# schematic.net
KiCad netlist of a schematic drawn in Altium Designer
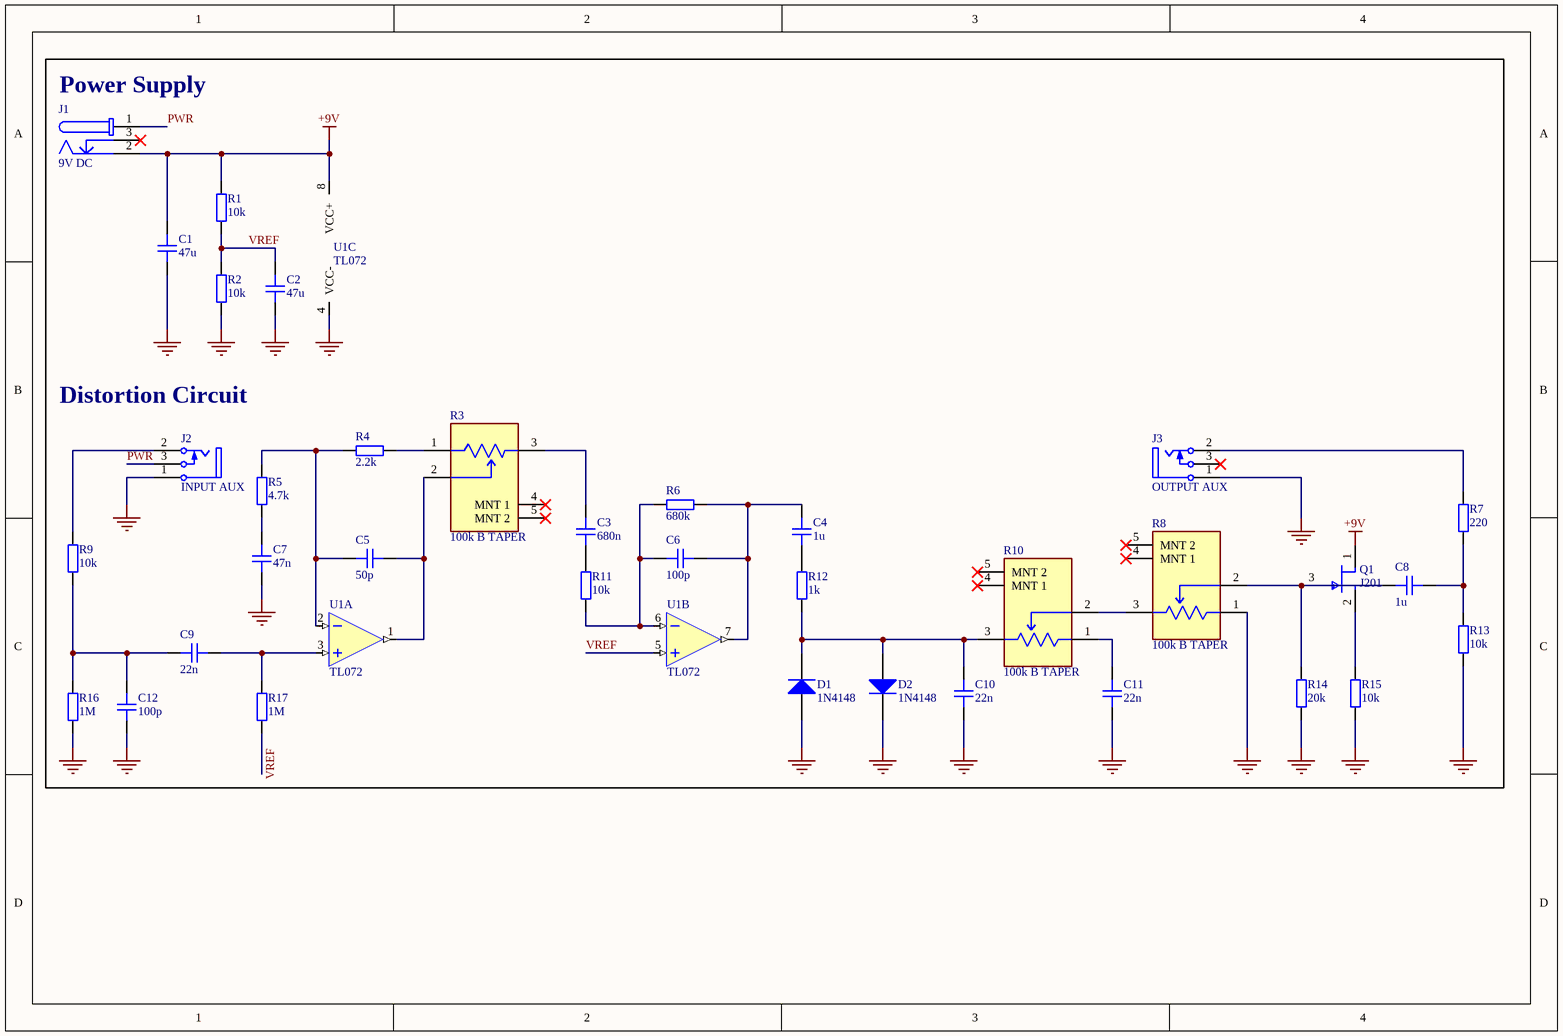
[diagram p0: schematic.SchDoc]

(export (version "E")
  (design (tool "Eeschema 10.0.6"))
  (components
    (comp (ref "C1")
      (value "47u")
      (footprint "CAP_0603")
      (description "Capacitor SMD 0603")
      (libsource (lib "Schematic-Lib-PhilsLab") (part "CAP_0603"))
    )
    (comp (ref "C2")
      (value "47u")
      (footprint "CAP_0603")
      (description "Capacitor SMD 0603")
      (libsource (lib "Schematic-Lib-PhilsLab") (part "CAP_0603"))
    )
    (comp (ref "C3")
      (value "680n")
      (footprint "CAP_0603")
      (description "Capacitor SMD 0603")
      (libsource (lib "Schematic-Lib-PhilsLab") (part "CAP_0603"))
    )
    (comp (ref "C4")
      (value "1u")
      (footprint "CAP_0603")
      (description "Capacitor SMD 0603")
      (libsource (lib "Schematic-Lib-PhilsLab") (part "CAP_0603"))
    )
    (comp (ref "C5")
      (value "50p")
      (footprint "CAP_0603")
      (description "Capacitor SMD 0603")
      (libsource (lib "Schematic-Lib-PhilsLab") (part "CAP_0603"))
    )
    (comp (ref "C6")
      (value "100p")
      (footprint "CAP_0603")
      (description "Capacitor SMD 0603")
      (libsource (lib "Schematic-Lib-PhilsLab") (part "CAP_0603"))
    )
    (comp (ref "C7")
      (value "47n")
      (footprint "CAP_0603")
      (description "Capacitor SMD 0603")
      (libsource (lib "Schematic-Lib-PhilsLab") (part "CAP_0603"))
    )
    (comp (ref "C8")
      (value "1u")
      (footprint "CAP_0603")
      (description "Capacitor SMD 0603")
      (libsource (lib "Schematic-Lib-PhilsLab") (part "CAP_0603"))
    )
    (comp (ref "C9")
      (value "22n")
      (footprint "CAP_0603")
      (description "Capacitor SMD 0603")
      (libsource (lib "Schematic-Lib-PhilsLab") (part "CAP_0603"))
    )
    (comp (ref "C10")
      (value "22n")
      (footprint "CAP_0603")
      (description "Capacitor SMD 0603")
      (libsource (lib "Schematic-Lib-PhilsLab") (part "CAP_0603"))
    )
    (comp (ref "C11")
      (value "22n")
      (footprint "CAP_0603")
      (description "Capacitor SMD 0603")
      (libsource (lib "Schematic-Lib-PhilsLab") (part "CAP_0603"))
    )
    (comp (ref "C12")
      (value "100p")
      (footprint "CAP_0603")
      (description "Capacitor SMD 0603")
      (libsource (lib "Schematic-Lib-PhilsLab") (part "CAP_0603"))
    )
    (comp (ref "D1")
      (value "1N4148")
      (footprint "DIOD-SOD323-2-A_V")
      (description "Fast Switching Diode, 75 V, 0.3 A, -65 to 150 degC, 2-Pin SOD323, RoHS, Tape and Reel")
      (libsource (lib "Altium Content Vault") (part "D-AK-2"))
    )
    (comp (ref "D2")
      (value "1N4148")
      (footprint "DIOD-SOD323-2-A_V")
      (description "Fast Switching Diode, 75 V, 0.3 A, -65 to 150 degC, 2-Pin SOD323, RoHS, Tape and Reel")
      (libsource (lib "Altium Content Vault") (part "D-AK-2"))
    )
    (comp (ref "J1")
      (value "9V DC")
      (footprint "694106301002")
      (libsource (lib "Altium Content Vault") (part "DC Power Jack"))
    )
    (comp (ref "J2")
      (value "INPUT AUX")
      (footprint "SWIT-PJRAN1X1U01X_V")
      (description "Female Phono Jack, 3 Position, Height 13 mm, Tail Length 4 mm, RoHS, Bulk")
      (fields (field (name "TOLERANCE") "10%"))
      (libsource (lib "Altium Content Vault") (part "JACK-2CD3-TN"))
    )
    (comp (ref "J3")
      (value "OUTPUT AUX")
      (footprint "SWIT-PJRAN1X1U01X_V")
      (description "Female Phono Jack, 3 Position, Height 13 mm, Tail Length 4 mm, RoHS, Bulk")
      (fields (field (name "TOLERANCE") "10%"))
      (libsource (lib "Altium Content Vault") (part "JACK-2CD3-TN"))
    )
    (comp (ref "Q1")
      (value "J201")
      (footprint "FP-318BM-IPC_C")
      (description "JFET N-CH 40V 350MW SOT23")
      (fields
        (field (name "MANUFACTURER") "ON Semiconductor")
        (field (name "OCTOPART") "https://octopart.com/mmbfj201-on+semiconductor-84330255")
      )
      (libsource (lib "Altium Content Vault") (part "14398f7355be6f33287877db3ee21c7"))
    )
    (comp (ref "R1")
      (value "10k")
      (footprint "RES_0603")
      (description "Resistor SMD 0603")
      (libsource (lib "Schematic-Lib-PhilsLab") (part "RES_0603"))
    )
    (comp (ref "R2")
      (value "10k")
      (footprint "RES_0603")
      (description "Resistor SMD 0603")
      (libsource (lib "Schematic-Lib-PhilsLab") (part "RES_0603"))
    )
    (comp (ref "R3")
      (value "100k B TAPER")
      (footprint "FP-PTV09A-4-MFG")
      (description "POT 10K OHM 1/20W CARBON LINEAR")
      (fields (field (name "MANUFACTURER PART NUMBER") "PTV09A-4020U-B103") (field (name "TOLERANCE") "20%"))
      (libsource (lib "") (part "3454c451b146ec4d4239c7813666f62_1"))
    )
    (comp (ref "R4")
      (value "2.2k")
      (footprint "RES_0603")
      (description "Resistor SMD 0603")
      (libsource (lib "Schematic-Lib-PhilsLab") (part "RES_0603"))
    )
    (comp (ref "R5")
      (value "4.7k")
      (footprint "RES_0603")
      (description "Resistor SMD 0603")
      (libsource (lib "Schematic-Lib-PhilsLab") (part "RES_0603"))
    )
    (comp (ref "R6")
      (value "680k")
      (footprint "RES_0603")
      (description "Resistor SMD 0603")
      (libsource (lib "Schematic-Lib-PhilsLab") (part "RES_0603"))
    )
    (comp (ref "R7")
      (value "220")
      (footprint "RES_0603")
      (description "Resistor SMD 0603")
      (libsource (lib "Schematic-Lib-PhilsLab") (part "RES_0603"))
    )
    (comp (ref "R8")
      (value "100k B TAPER")
      (footprint "FP-PTV09A-4-MFG")
      (description "POT 10K OHM 1/20W CARBON LINEAR")
      (fields (field (name "MANUFACTURER PART NUMBER") "PTV09A-4020U-B103") (field (name "TOLERANCE") "20%"))
      (libsource (lib "Altium Content Vault") (part "3454c451b146ec4d4239c7813666f62"))
    )
    (comp (ref "R9")
      (value "10k")
      (footprint "RES_0603")
      (description "Resistor SMD 0603")
      (libsource (lib "Schematic-Lib-PhilsLab") (part "RES_0603"))
    )
    (comp (ref "R10")
      (value "100k B TAPER")
      (footprint "FP-PTV09A-4-MFG")
      (description "POT 10K OHM 1/20W CARBON LINEAR")
      (fields (field (name "MANUFACTURER PART NUMBER") "PTV09A-4020U-B103") (field (name "TOLERANCE") "20%"))
      (libsource (lib "Altium Content Vault") (part "3454c451b146ec4d4239c7813666f62"))
    )
    (comp (ref "R11")
      (value "10k")
      (footprint "RES_0603")
      (description "Resistor SMD 0603")
      (libsource (lib "Schematic-Lib-PhilsLab") (part "RES_0603"))
    )
    (comp (ref "R12")
      (value "1k")
      (footprint "RES_0603")
      (description "Resistor SMD 0603")
      (libsource (lib "Schematic-Lib-PhilsLab") (part "RES_0603"))
    )
    (comp (ref "R13")
      (value "10k")
      (footprint "RES_0603")
      (description "Resistor SMD 0603")
      (libsource (lib "Schematic-Lib-PhilsLab") (part "RES_0603"))
    )
    (comp (ref "R14")
      (value "20k")
      (footprint "RES_0603")
      (description "Resistor SMD 0603")
      (libsource (lib "Schematic-Lib-PhilsLab") (part "RES_0603"))
    )
    (comp (ref "R15")
      (value "10k")
      (footprint "RES_0603")
      (description "Resistor SMD 0603")
      (libsource (lib "Schematic-Lib-PhilsLab") (part "RES_0603"))
    )
    (comp (ref "R16")
      (value "1M")
      (footprint "RES_0603")
      (description "Resistor SMD 0603")
      (libsource (lib "Schematic-Lib-PhilsLab") (part "RES_0603"))
    )
    (comp (ref "R17")
      (value "1M")
      (footprint "RES_0603")
      (description "Resistor SMD 0603")
      (libsource (lib "Schematic-Lib-PhilsLab") (part "RES_0603"))
    )
    (comp (ref "U1")
      (value "TL072")
      (footprint "SOIC-8")
      (description "Dual JFET Low-Noise Operational Amplifiers")
      (fields
        (field (name "MANUFACTURER") "STMicroelectronics")
        (field (name "MANUFACTURER PART NUMBER") "TL072CDT")
      )
      (libsource (lib "Schematic-Lib-PhilsLab") (part "TL072CDT"))
    )
  )
  (nets
    (net (code "1") (name "+9V") (class "Default")
      (node (ref "C1") (pin "1") (pinfunction "1_1") (pintype "passive"))
      (node (ref "J1") (pin "2") (pinfunction "2_2") (pintype "passive"))
      (node (ref "Q1") (pin "1") (pinfunction "D_1") (pintype "passive"))
      (node (ref "R1") (pin "2") (pinfunction "2_2") (pintype "passive"))
      (node (ref "U1") (pin "8") (pinfunction "VCC+_8") (pintype "passive"))
    )
    (net (code "2") (name "/PWR") (class "Default")
      (node (ref "J1") (pin "1") (pinfunction "1_1") (pintype "passive"))
      (node (ref "J2") (pin "3") (pinfunction "SHUNT_3") (pintype "passive"))
    )
    (net (code "3") (name "/VREF") (class "Default")
      (node (ref "C2") (pin "1") (pinfunction "1_1") (pintype "passive"))
      (node (ref "R1") (pin "1") (pinfunction "1_1") (pintype "passive"))
      (node (ref "R17") (pin "1") (pinfunction "1_1") (pintype "passive"))
      (node (ref "R2") (pin "2") (pinfunction "2_2") (pintype "passive"))
      (node (ref "U1") (pin "5") (pinfunction "2IN+_5") (pintype "input"))
    )
    (net (code "4") (name "GND") (class "Default")
      (node (ref "C1") (pin "2") (pinfunction "2_2") (pintype "passive"))
      (node (ref "C10") (pin "1") (pinfunction "1_1") (pintype "passive"))
      (node (ref "C11") (pin "1") (pinfunction "1_1") (pintype "passive"))
      (node (ref "C12") (pin "1") (pinfunction "1_1") (pintype "passive"))
      (node (ref "C2") (pin "2") (pinfunction "2_2") (pintype "passive"))
      (node (ref "C7") (pin "2") (pinfunction "2_2") (pintype "passive"))
      (node (ref "D1") (pin "1") (pinfunction "A_1") (pintype "passive"))
      (node (ref "D2") (pin "2") (pinfunction "K_2") (pintype "passive"))
      (node (ref "J2") (pin "1") (pinfunction "SLEEVE_1") (pintype "passive"))
      (node (ref "J3") (pin "1") (pinfunction "SLEEVE_1") (pintype "passive"))
      (node (ref "R13") (pin "1") (pinfunction "1_1") (pintype "passive"))
      (node (ref "R14") (pin "1") (pinfunction "1_1") (pintype "passive"))
      (node (ref "R15") (pin "1") (pinfunction "1_1") (pintype "passive"))
      (node (ref "R16") (pin "1") (pinfunction "1_1") (pintype "passive"))
      (node (ref "R2") (pin "1") (pinfunction "1_1") (pintype "passive"))
      (node (ref "R8") (pin "1") (pinfunction "1_1") (pintype "passive"))
      (node (ref "U1") (pin "4") (pinfunction "VCC-_4") (pintype "passive"))
    )
    (net (code "5") (name "Net-(C3-Pad1)") (class "Default")
      (node (ref "C3") (pin "1") (pinfunction "1_1") (pintype "passive"))
      (node (ref "R3") (pin "3") (pinfunction "3_3") (pintype "passive"))
    )
    (net (code "6") (name "Net-(C3-Pad2)") (class "Default")
      (node (ref "C3") (pin "2") (pinfunction "2_2") (pintype "passive"))
      (node (ref "R11") (pin "2") (pinfunction "2_2") (pintype "passive"))
    )
    (net (code "7") (name "Net-(C4-Pad1)") (class "Default")
      (node (ref "C4") (pin "1") (pinfunction "1_1") (pintype "passive"))
      (node (ref "R12") (pin "2") (pinfunction "2_2") (pintype "passive"))
    )
    (net (code "8") (name "Net-(C7-Pad1)") (class "Default")
      (node (ref "C7") (pin "1") (pinfunction "1_1") (pintype "passive"))
      (node (ref "R5") (pin "1") (pinfunction "1_1") (pintype "passive"))
    )
    (net (code "9") (name "Net-(C8-Pad1)") (class "Default")
      (node (ref "C8") (pin "1") (pinfunction "1_1") (pintype "passive"))
      (node (ref "R13") (pin "2") (pinfunction "2_2") (pintype "passive"))
      (node (ref "R7") (pin "1") (pinfunction "1_1") (pintype "passive"))
    )
    (net (code "10") (name "Net-(C11-Pad2)") (class "Default")
      (node (ref "C11") (pin "2") (pinfunction "2_2") (pintype "passive"))
      (node (ref "R10") (pin "1") (pinfunction "1_1") (pintype "passive"))
    )
    (net (code "11") (name "Net-(C12-Pad2)") (class "Default")
      (node (ref "C12") (pin "2") (pinfunction "2_2") (pintype "passive"))
      (node (ref "C9") (pin "2") (pinfunction "2_2") (pintype "passive"))
      (node (ref "R16") (pin "2") (pinfunction "2_2") (pintype "passive"))
      (node (ref "R9") (pin "1") (pinfunction "1_1") (pintype "passive"))
    )
    (net (code "12") (name "Net-(D1-K)") (class "Default")
      (node (ref "C10") (pin "2") (pinfunction "2_2") (pintype "passive"))
      (node (ref "D1") (pin "2") (pinfunction "K_2") (pintype "passive"))
      (node (ref "D2") (pin "1") (pinfunction "A_1") (pintype "passive"))
      (node (ref "R10") (pin "3") (pinfunction "3_3") (pintype "passive"))
      (node (ref "R12") (pin "1") (pinfunction "1_1") (pintype "passive"))
    )
    (net (code "13") (name "Net-(J2-TIP)") (class "Default")
      (node (ref "J2") (pin "2") (pinfunction "TIP_2") (pintype "passive"))
      (node (ref "R9") (pin "2") (pinfunction "2_2") (pintype "passive"))
    )
    (net (code "14") (name "Net-(J3-TIP)") (class "Default")
      (node (ref "J3") (pin "2") (pinfunction "TIP_2") (pintype "passive"))
      (node (ref "R7") (pin "2") (pinfunction "2_2") (pintype "passive"))
    )
    (net (code "15") (name "Net-(Q1-G)") (class "Default")
      (node (ref "C8") (pin "2") (pinfunction "2_2") (pintype "passive"))
      (node (ref "Q1") (pin "3") (pinfunction "G_3") (pintype "passive"))
      (node (ref "R14") (pin "2") (pinfunction "2_2") (pintype "passive"))
      (node (ref "R8") (pin "2") (pinfunction "2_2") (pintype "passive"))
    )
    (net (code "16") (name "Net-(Q1-S)") (class "Default")
      (node (ref "Q1") (pin "2") (pinfunction "S_2") (pintype "passive"))
      (node (ref "R15") (pin "2") (pinfunction "2_2") (pintype "passive"))
    )
    (net (code "17") (name "Net-(R3-Pad1)") (class "Default")
      (node (ref "R3") (pin "1") (pinfunction "1_1") (pintype "passive"))
      (node (ref "R4") (pin "1") (pinfunction "1_1") (pintype "passive"))
    )
    (net (code "18") (name "Net-(R10-Pad2)") (class "Default")
      (node (ref "R10") (pin "2") (pinfunction "2_2") (pintype "passive"))
      (node (ref "R8") (pin "3") (pinfunction "3_3") (pintype "passive"))
    )
    (net (code "19") (name "Net-(U1A-1IN+)") (class "Default")
      (node (ref "C9") (pin "1") (pinfunction "1_1") (pintype "passive"))
      (node (ref "R17") (pin "2") (pinfunction "2_2") (pintype "passive"))
      (node (ref "U1") (pin "3") (pinfunction "1IN+_3") (pintype "input"))
    )
    (net (code "20") (name "Net-(U1A-1IN-)") (class "Default")
      (node (ref "C5") (pin "2") (pinfunction "2_2") (pintype "passive"))
      (node (ref "R4") (pin "2") (pinfunction "2_2") (pintype "passive"))
      (node (ref "R5") (pin "2") (pinfunction "2_2") (pintype "passive"))
      (node (ref "U1") (pin "2") (pinfunction "1IN-_2") (pintype "input"))
    )
    (net (code "21") (name "Net-(U1A-1OUT)") (class "Default")
      (node (ref "C5") (pin "1") (pinfunction "1_1") (pintype "passive"))
      (node (ref "R3") (pin "2") (pinfunction "2_2") (pintype "passive"))
      (node (ref "U1") (pin "1") (pinfunction "1OUT_1") (pintype "output"))
    )
    (net (code "22") (name "Net-(U1B-2IN-)") (class "Default")
      (node (ref "C6") (pin "2") (pinfunction "2_2") (pintype "passive"))
      (node (ref "R11") (pin "1") (pinfunction "1_1") (pintype "passive"))
      (node (ref "R6") (pin "2") (pinfunction "2_2") (pintype "passive"))
      (node (ref "U1") (pin "6") (pinfunction "2IN-_6") (pintype "input"))
    )
    (net (code "23") (name "Net-(U1B-2OUT)") (class "Default")
      (node (ref "C4") (pin "2") (pinfunction "2_2") (pintype "passive"))
      (node (ref "C6") (pin "1") (pinfunction "1_1") (pintype "passive"))
      (node (ref "R6") (pin "1") (pinfunction "1_1") (pintype "passive"))
      (node (ref "U1") (pin "7") (pinfunction "2OUT_7") (pintype "output"))
    )
    (net (code "24") (name "unconnected-(J1-Pad3)") (class "Default")
      (node (ref "J1") (pin "3") (pinfunction "3_3") (pintype "passive+no_connect"))
    )
    (net (code "25") (name "unconnected-(J3-SHUNT-Pad3)") (class "Default")
      (node (ref "J3") (pin "3") (pinfunction "SHUNT_3") (pintype "passive+no_connect"))
    )
    (net (code "26") (name "unconnected-(R3-MNT_1-Pad4)") (class "Default")
      (node (ref "R3") (pin "4") (pinfunction "MNT_1_4") (pintype "passive+no_connect"))
    )
    (net (code "27") (name "unconnected-(R3-MNT_2-Pad5)") (class "Default")
      (node (ref "R3") (pin "5") (pinfunction "MNT_2_5") (pintype "passive+no_connect"))
    )
    (net (code "28") (name "unconnected-(R8-MNT_1-Pad4)") (class "Default")
      (node (ref "R8") (pin "4") (pinfunction "MNT_1_4") (pintype "passive+no_connect"))
    )
    (net (code "29") (name "unconnected-(R8-MNT_2-Pad5)") (class "Default")
      (node (ref "R8") (pin "5") (pinfunction "MNT_2_5") (pintype "passive+no_connect"))
    )
    (net (code "30") (name "unconnected-(R10-MNT_1-Pad4)") (class "Default")
      (node (ref "R10") (pin "4") (pinfunction "MNT_1_4") (pintype "passive+no_connect"))
    )
    (net (code "31") (name "unconnected-(R10-MNT_2-Pad5)") (class "Default")
      (node (ref "R10") (pin "5") (pinfunction "MNT_2_5") (pintype "passive+no_connect"))
    )
  )
)
